# sim900min11.net
KiCad netlist of a schematic drawn in EAGLE
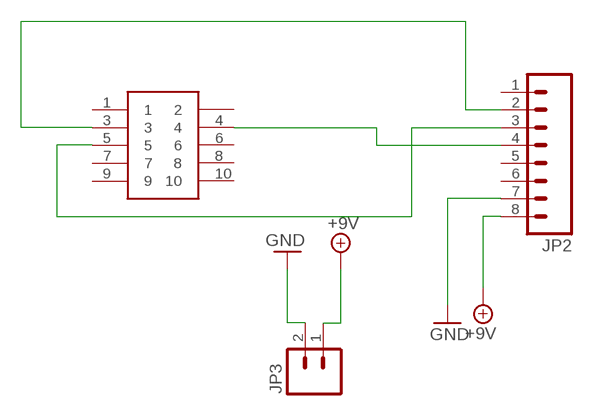
[diagram p0: schematic, sheet 1]

(export (version "E")
  (design (tool "Eeschema 10.0.6"))
  (components
    (comp (ref "JP2")
      (value "M081X08")
      (footprint "eagle-import:1X08")
      (libsource (lib "eagle-import") (part "M081X08"))
    )
    (comp (ref "JP3")
      (value "M02JST-PTH-2-KIT")
      (footprint "eagle-import:JST-2-PTH-KIT")
      (libsource (lib "eagle-import") (part "M02JST-PTH-2-KIT"))
    )
    (comp (ref "U$1")
      (value "SHF105SM")
      (footprint "eagle-import:SHF105DSM")
      (libsource (lib "eagle-import") (part "SHF105SM"))
    )
  )
  (nets
    (net (code "1") (name "+9V") (class "Default")
      (node (ref "JP2") (pin "8") (pinfunction "8_8") (pintype "passive"))
      (node (ref "JP3") (pin "1") (pinfunction "1_1") (pintype "passive"))
    )
    (net (code "2") (name "GND") (class "Default")
      (node (ref "JP2") (pin "7") (pinfunction "7_7") (pintype "passive"))
      (node (ref "JP3") (pin "2") (pinfunction "2_2") (pintype "passive"))
    )
    (net (code "3") (name "Net-(JP2-Pad2)") (class "Default")
      (node (ref "JP2") (pin "2") (pinfunction "2_2") (pintype "passive"))
      (node (ref "U$1") (pin "3") (pinfunction "3_3") (pintype "passive"))
    )
    (net (code "4") (name "Net-(JP2-Pad3)") (class "Default")
      (node (ref "JP2") (pin "3") (pinfunction "3_3") (pintype "passive"))
      (node (ref "U$1") (pin "5") (pinfunction "5_5") (pintype "passive"))
    )
    (net (code "5") (name "Net-(JP2-Pad4)") (class "Default")
      (node (ref "JP2") (pin "4") (pinfunction "4_4") (pintype "passive"))
      (node (ref "U$1") (pin "4") (pinfunction "4_4") (pintype "passive"))
    )
    (net (code "6") (name "unconnected-(JP2-Pad1)") (class "Default")
      (node (ref "JP2") (pin "1") (pinfunction "1_1") (pintype "passive"))
    )
    (net (code "7") (name "unconnected-(JP2-Pad5)") (class "Default")
      (node (ref "JP2") (pin "5") (pinfunction "5_5") (pintype "passive"))
    )
    (net (code "8") (name "unconnected-(JP2-Pad6)") (class "Default")
      (node (ref "JP2") (pin "6") (pinfunction "6_6") (pintype "passive"))
    )
    (net (code "9") (name "unconnected-(U$1-Pad1)") (class "Default")
      (node (ref "U$1") (pin "1") (pinfunction "1_1") (pintype "passive"))
    )
    (net (code "10") (name "unconnected-(U$1-Pad2)") (class "Default")
      (node (ref "U$1") (pin "2") (pinfunction "2_2") (pintype "passive"))
    )
    (net (code "11") (name "unconnected-(U$1-Pad6)") (class "Default")
      (node (ref "U$1") (pin "6") (pinfunction "6_6") (pintype "passive"))
    )
    (net (code "12") (name "unconnected-(U$1-Pad7)") (class "Default")
      (node (ref "U$1") (pin "7") (pinfunction "7_7") (pintype "passive"))
    )
    (net (code "13") (name "unconnected-(U$1-Pad8)") (class "Default")
      (node (ref "U$1") (pin "8") (pinfunction "8_8") (pintype "passive"))
    )
    (net (code "14") (name "unconnected-(U$1-Pad9)") (class "Default")
      (node (ref "U$1") (pin "9") (pinfunction "9_9") (pintype "passive"))
    )
    (net (code "15") (name "unconnected-(U$1-Pad10)") (class "Default")
      (node (ref "U$1") (pin "10") (pinfunction "10_10") (pintype "passive"))
    )
  )
)
